# RAMP_V1-4.net
KiCad netlist of a schematic drawn in Altium Designer
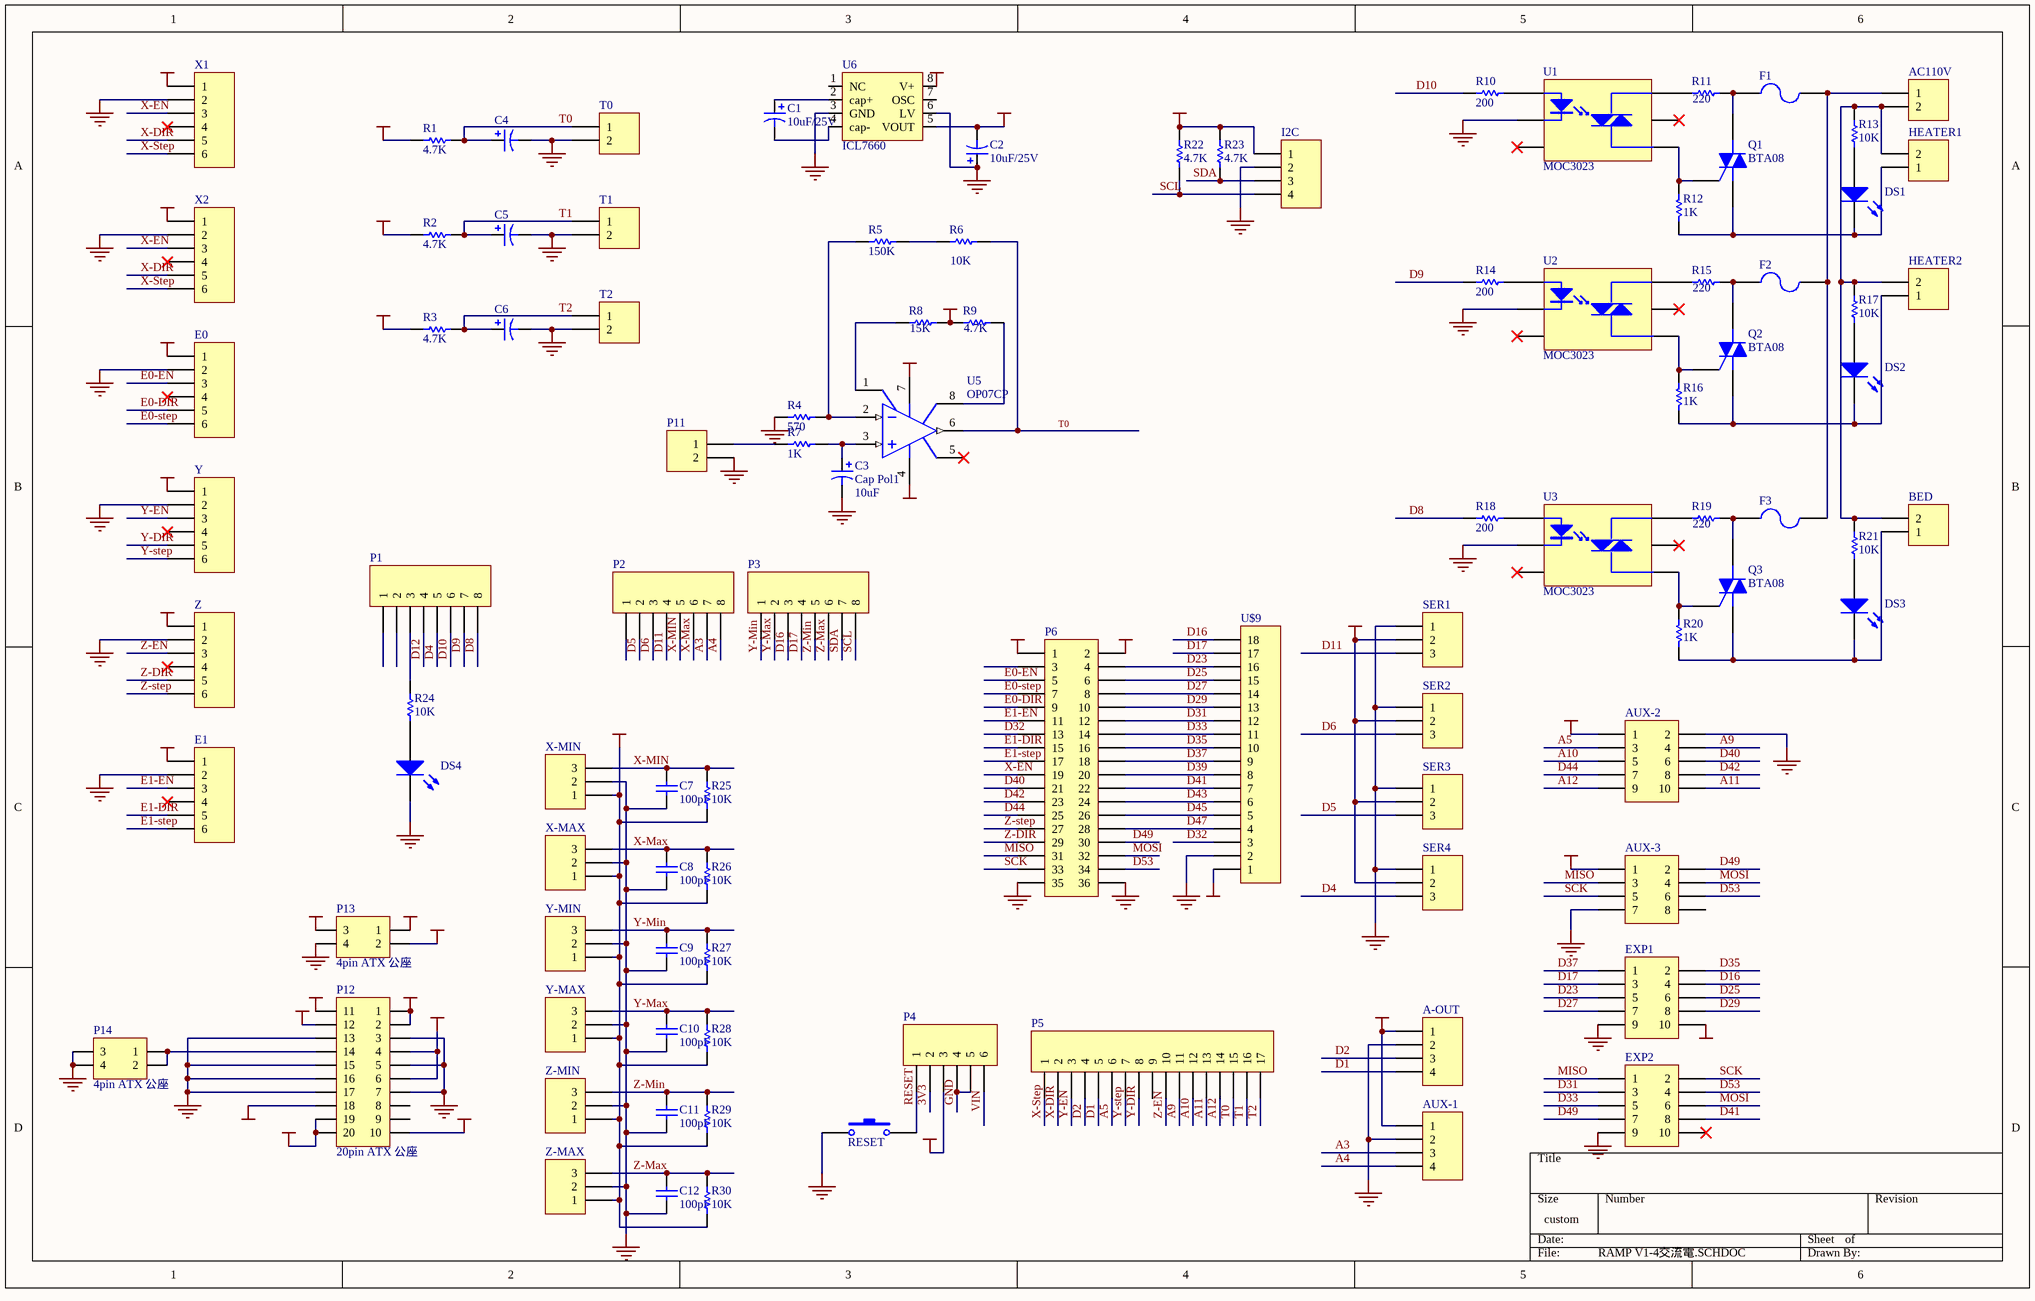
[diagram p0: RAMP V1-4交流電.SCHDOC]

(export (version "E")
  (design (tool "Eeschema 10.0.6"))
  (components
    (comp (ref "A-OUT")
      (value "Header 4")
      (footprint "HDR1X4")
      (description "Header, 4-Pin")
      (libsource (lib "Miscellaneous Connectors") (part "Header 4"))
    )
    (comp (ref "AC110V")
      (value "Header 2")
      (footprint "2PIN端子-1")
      (description "Header, 2-Pin")
      (libsource (lib "") (part "Header 2_2"))
    )
    (comp (ref "AUX-1")
      (value "Header 4")
      (footprint "HDR1X4")
      (description "Header, 4-Pin")
      (libsource (lib "Miscellaneous Connectors") (part "Header 4"))
    )
    (comp (ref "AUX-2")
      (value "Header 5X2")
      (footprint "HDR2X5")
      (description "Header, 5-Pin, Dual row")
      (libsource (lib "Miscellaneous Connectors") (part "Header 5X2"))
    )
    (comp (ref "AUX-3")
      (value "Header 4X2")
      (footprint "HDR2X4")
      (description "Header, 4-Pin, Dual row")
      (libsource (lib "Miscellaneous Connectors") (part "Header 4X2"))
    )
    (comp (ref "BED")
      (value "Header 2")
      (footprint "2PIN端子-1")
      (description "Header, 2-Pin")
      (libsource (lib "Miscellaneous Connectors") (part "Header 2"))
    )
    (comp (ref "C1")
      (value "10uF/25V")
      (footprint "CAPPR5-5x5")
      (description "Polarized Capacitor (Radial)")
      (fields (field (name "Comment") "Cap Pol1"))
      (libsource (lib "Miscellaneous Devices") (part "Cap Pol1"))
    )
    (comp (ref "C2")
      (value "10uF/25V")
      (footprint "CAPPR5-5x5")
      (description "Polarized Capacitor (Radial)")
      (fields (field (name "Comment") "Cap Pol1"))
      (libsource (lib "Miscellaneous Devices") (part "Cap Pol1"))
    )
    (comp (ref "C3")
      (value "Cap Pol1")
      (footprint "CAPPR5-5x5")
      (description "Polarized Capacitor (Radial)")
      (fields (field (name "ALTIUM_VALUE") "10uF"))
      (libsource (lib "Miscellaneous Devices") (part "Cap Pol1"))
    )
    (comp (ref "C4")
      (value "Cap Pol1")
      (footprint "CAPPR2-5x6.8")
      (description "Polarized Capacitor (Radial)")
      (libsource (lib "Miscellaneous Devices") (part "Cap Pol1"))
    )
    (comp (ref "C5")
      (value "Cap Pol1")
      (footprint "CAPPR2-5x6.8")
      (description "Polarized Capacitor (Radial)")
      (libsource (lib "Miscellaneous Devices") (part "Cap Pol1"))
    )
    (comp (ref "C6")
      (value "Cap Pol1")
      (footprint "CAPPR2-5x6.8")
      (description "Polarized Capacitor (Radial)")
      (libsource (lib "Miscellaneous Devices") (part "Cap Pol1"))
    )
    (comp (ref "C7")
      (value "100pF")
      (footprint "CAPR2.54-5.1x3.2")
      (description "Capacitor")
      (fields (field (name "Comment") "Cap"))
      (libsource (lib "Miscellaneous Devices") (part "Cap"))
    )
    (comp (ref "C8")
      (value "100pF")
      (footprint "CAPR2.54-5.1x3.2")
      (description "Capacitor")
      (fields (field (name "Comment") "Cap"))
      (libsource (lib "Miscellaneous Devices") (part "Cap"))
    )
    (comp (ref "C9")
      (value "100pF")
      (footprint "CAPR2.54-5.1x3.2")
      (description "Capacitor")
      (fields (field (name "Comment") "Cap"))
      (libsource (lib "Miscellaneous Devices") (part "Cap"))
    )
    (comp (ref "C10")
      (value "100pF")
      (footprint "CAPR2.54-5.1x3.2")
      (description "Capacitor")
      (fields (field (name "Comment") "Cap"))
      (libsource (lib "Miscellaneous Devices") (part "Cap"))
    )
    (comp (ref "C11")
      (value "100pF")
      (footprint "CAPR2.54-5.1x3.2")
      (description "Capacitor")
      (fields (field (name "Comment") "Cap"))
      (libsource (lib "Miscellaneous Devices") (part "Cap"))
    )
    (comp (ref "C12")
      (value "100pF")
      (footprint "CAPR2.54-5.1x3.2")
      (description "Capacitor")
      (fields (field (name "Comment") "Cap"))
      (libsource (lib "Miscellaneous Devices") (part "Cap"))
    )
    (comp (ref "DS1")
      (value "LED0")
      (footprint "LED-2")
      (description "Typical INFRARED GaAs LED")
      (libsource (lib "Miscellaneous Devices") (part "LED0"))
    )
    (comp (ref "DS2")
      (value "LED0")
      (footprint "LED-2")
      (description "Typical INFRARED GaAs LED")
      (libsource (lib "Miscellaneous Devices") (part "LED0"))
    )
    (comp (ref "DS3")
      (value "LED0")
      (footprint "LED-2")
      (description "Typical INFRARED GaAs LED")
      (libsource (lib "Miscellaneous Devices") (part "LED0"))
    )
    (comp (ref "DS4")
      (value "LED0")
      (footprint "LED-2")
      (description "Typical INFRARED GaAs LED")
      (libsource (lib "Miscellaneous Devices") (part "LED0"))
    )
    (comp (ref "E0")
      (value "Header 6")
      (footprint "2.54mm 6pin")
      (description "Header, 6-Pin")
      (libsource (lib "Miscellaneous Connectors") (part "Header 6"))
    )
    (comp (ref "E1")
      (value "Header 6")
      (footprint "2.54mm 6pin")
      (description "Header, 6-Pin")
      (libsource (lib "Miscellaneous Connectors") (part "Header 6"))
    )
    (comp (ref "EXP1")
      (value "Header 5X2")
      (footprint "10pin牛角公座")
      (description "Header, 5-Pin, Dual row")
      (libsource (lib "Miscellaneous Connectors") (part "Header 5X2"))
    )
    (comp (ref "EXP2")
      (value "Header 5X2")
      (footprint "10pin牛角公座")
      (description "Header, 5-Pin, Dual row")
      (libsource (lib "Miscellaneous Connectors") (part "Header 5X2"))
    )
    (comp (ref "F1")
      (value "Fuse 2")
      (footprint "保險絲座")
      (description "Fuse")
      (libsource (lib "Miscellaneous Devices") (part "Fuse 2"))
    )
    (comp (ref "F2")
      (value "Fuse 2")
      (footprint "保險絲座")
      (description "Fuse")
      (libsource (lib "Miscellaneous Devices") (part "Fuse 2"))
    )
    (comp (ref "F3")
      (value "Fuse 2")
      (footprint "保險絲座")
      (description "Fuse")
      (libsource (lib "Miscellaneous Devices") (part "Fuse 2"))
    )
    (comp (ref "HEATER1")
      (value "Header 2")
      (footprint "2PIN端子-1")
      (description "Header, 2-Pin")
      (libsource (lib "Miscellaneous Connectors") (part "Header 2"))
    )
    (comp (ref "HEATER2")
      (value "Header 2")
      (footprint "2PIN端子-1")
      (description "Header, 2-Pin")
      (libsource (lib "Miscellaneous Connectors") (part "Header 2"))
    )
    (comp (ref "I2C")
      (value "Header 4")
      (footprint "HDR1X4")
      (description "Header, 4-Pin")
      (libsource (lib "Miscellaneous Connectors") (part "Header 4"))
    )
    (comp (ref "P1")
      (value "Header 8")
      (footprint "HDR1X8")
      (description "Header, 8-Pin")
      (libsource (lib "") (part "Header 8_1"))
    )
    (comp (ref "P2")
      (value "Header 8")
      (footprint "HDR1X8")
      (description "Header, 8-Pin")
      (libsource (lib "Miscellaneous Connectors") (part "Header 8"))
    )
    (comp (ref "P3")
      (value "Header 8")
      (footprint "HDR1X8")
      (description "Header, 8-Pin")
      (libsource (lib "Miscellaneous Connectors") (part "Header 8"))
    )
    (comp (ref "P4")
      (value "Header 6")
      (footprint "HDR1X6")
      (description "Header, 6-Pin")
      (libsource (lib "") (part "Header 6_1"))
    )
    (comp (ref "P5")
      (value "Header 17")
      (footprint "HDR1X17")
      (description "Header, 17-Pin")
      (libsource (lib "Miscellaneous Connectors") (part "Header 17"))
    )
    (comp (ref "P6")
      (value "Header 18X2")
      (footprint "HDR2X18")
      (description "Header, 18-Pin, Dual row")
      (libsource (lib "Miscellaneous Connectors") (part "Header 18X2"))
    )
    (comp (ref "P11")
      (value "Header 2")
      (footprint "2PINºÝ¤l¥x¦³¦Õ")
      (description "Header, 2-Pin")
      (libsource (lib "") (part "Header 2_1"))
    )
    (comp (ref "P12")
      (value "20pin ATX 公座")
      (footprint "4.2mm 20pin")
      (libsource (lib "mydata") (part "20pin ATX 公座"))
    )
    (comp (ref "P13")
      (value "4pin ATX 公座")
      (footprint "4.2mm 4pin")
      (libsource (lib "mydata") (part "4pin ATX 公座"))
    )
    (comp (ref "P14")
      (value "4pin ATX 公座")
      (footprint "4.2mm 4pin")
      (libsource (lib "mydata") (part "4pin ATX 公座"))
    )
    (comp (ref "Q1")
      (value "BTA08")
      (footprint "SFM-T3/X1.6V")
      (description "Silicon Bidirectional Triode Thyristor")
      (libsource (lib "Miscellaneous Devices") (part "Triac"))
    )
    (comp (ref "Q2")
      (value "BTA08")
      (footprint "SFM-T3/X1.6V")
      (description "Silicon Bidirectional Triode Thyristor")
      (libsource (lib "Miscellaneous Devices") (part "Triac"))
    )
    (comp (ref "Q3")
      (value "BTA08")
      (footprint "SFM-T3/X1.6V")
      (description "Silicon Bidirectional Triode Thyristor")
      (libsource (lib "Miscellaneous Devices") (part "Triac"))
    )
    (comp (ref "R1")
      (value "4.7K")
      (footprint "AXIAL-0.3")
      (description "Resistor")
      (fields (field (name "Comment") "Res1"))
      (libsource (lib "Miscellaneous Devices") (part "Res1"))
    )
    (comp (ref "R2")
      (value "4.7K")
      (footprint "AXIAL-0.3")
      (description "Resistor")
      (fields (field (name "Comment") "Res1"))
      (libsource (lib "Miscellaneous Devices") (part "Res1"))
    )
    (comp (ref "R3")
      (value "4.7K")
      (footprint "AXIAL-0.3")
      (description "Resistor")
      (fields (field (name "Comment") "Res1"))
      (libsource (lib "Miscellaneous Devices") (part "Res1"))
    )
    (comp (ref "R4")
      (value "570")
      (footprint "AXIAL-0.3")
      (description "Resistor")
      (fields (field (name "Comment") "Res1"))
      (libsource (lib "Miscellaneous Devices") (part "Res1"))
    )
    (comp (ref "R5")
      (value "150K")
      (footprint "AXIAL-0.3")
      (description "Resistor")
      (fields (field (name "Comment") "Res1"))
      (libsource (lib "Miscellaneous Devices") (part "Res1"))
    )
    (comp (ref "R6")
      (value "10K")
      (footprint "AXIAL-0.3")
      (description "Resistor")
      (fields (field (name "Comment") "Res1"))
      (libsource (lib "Miscellaneous Devices") (part "Res1"))
    )
    (comp (ref "R7")
      (value "1K")
      (footprint "AXIAL-0.3")
      (description "Resistor")
      (fields (field (name "Comment") "Res1"))
      (libsource (lib "Miscellaneous Devices") (part "Res1"))
    )
    (comp (ref "R8")
      (value "15K")
      (footprint "AXIAL-0.3")
      (description "Resistor")
      (fields (field (name "Comment") "Res1"))
      (libsource (lib "Miscellaneous Devices") (part "Res1"))
    )
    (comp (ref "R9")
      (value "4.7K")
      (footprint "AXIAL-0.3")
      (description "Resistor")
      (fields (field (name "Comment") "Res1"))
      (libsource (lib "Miscellaneous Devices") (part "Res1"))
    )
    (comp (ref "R10")
      (value "200")
      (footprint "AXIAL-0.4")
      (description "Resistor")
      (fields (field (name "Comment") "Res1"))
      (libsource (lib "Miscellaneous Devices") (part "Res1"))
    )
    (comp (ref "R11")
      (value "220")
      (footprint "AXIAL-0.7")
      (description "Resistor")
      (fields (field (name "Comment") "Res1"))
      (libsource (lib "Miscellaneous Devices") (part "Res1"))
    )
    (comp (ref "R12")
      (value "1K")
      (footprint "AXIAL-0.6")
      (description "Resistor")
      (fields (field (name "Comment") "Res1"))
      (libsource (lib "") (part "Res1_1"))
    )
    (comp (ref "R13")
      (value "10K")
      (footprint "AXIAL-0.3")
      (description "Resistor")
      (fields (field (name "Comment") "Res1"))
      (libsource (lib "Miscellaneous Devices") (part "Res1"))
    )
    (comp (ref "R14")
      (value "200")
      (footprint "AXIAL-0.4")
      (description "Resistor")
      (fields (field (name "Comment") "Res1"))
      (libsource (lib "Miscellaneous Devices") (part "Res1"))
    )
    (comp (ref "R15")
      (value "220")
      (footprint "AXIAL-0.7")
      (description "Resistor")
      (fields (field (name "Comment") "Res1"))
      (libsource (lib "Miscellaneous Devices") (part "Res1"))
    )
    (comp (ref "R16")
      (value "1K")
      (footprint "AXIAL-0.6")
      (description "Resistor")
      (fields (field (name "Comment") "Res1"))
      (libsource (lib "") (part "Res1_1"))
    )
    (comp (ref "R17")
      (value "10K")
      (footprint "AXIAL-0.3")
      (description "Resistor")
      (fields (field (name "Comment") "Res1"))
      (libsource (lib "Miscellaneous Devices") (part "Res1"))
    )
    (comp (ref "R18")
      (value "200")
      (footprint "AXIAL-0.4")
      (description "Resistor")
      (fields (field (name "Comment") "Res1"))
      (libsource (lib "Miscellaneous Devices") (part "Res1"))
    )
    (comp (ref "R19")
      (value "220")
      (footprint "AXIAL-0.7")
      (description "Resistor")
      (fields (field (name "Comment") "Res1"))
      (libsource (lib "Miscellaneous Devices") (part "Res1"))
    )
    (comp (ref "R20")
      (value "1K")
      (footprint "AXIAL-0.6")
      (description "Resistor")
      (fields (field (name "Comment") "Res1"))
      (libsource (lib "") (part "Res1_1"))
    )
    (comp (ref "R21")
      (value "10K")
      (footprint "AXIAL-0.3")
      (description "Resistor")
      (fields (field (name "Comment") "Res1"))
      (libsource (lib "Miscellaneous Devices") (part "Res1"))
    )
    (comp (ref "R22")
      (value "4.7K")
      (footprint "AXIAL-0.3")
      (description "Resistor")
      (fields (field (name "Comment") "Res1"))
      (libsource (lib "Miscellaneous Devices") (part "Res1"))
    )
    (comp (ref "R23")
      (value "4.7K")
      (footprint "AXIAL-0.3")
      (description "Resistor")
      (fields (field (name "Comment") "Res1"))
      (libsource (lib "Miscellaneous Devices") (part "Res1"))
    )
    (comp (ref "R24")
      (value "10K")
      (footprint "AXIAL-0.3")
      (description "Resistor")
      (fields (field (name "Comment") "Res1"))
      (libsource (lib "Miscellaneous Devices") (part "Res1"))
    )
    (comp (ref "R25")
      (value "10K")
      (footprint "AXIAL-0.3")
      (description "Resistor")
      (fields (field (name "Comment") "Res1"))
      (libsource (lib "Miscellaneous Devices") (part "Res1"))
    )
    (comp (ref "R26")
      (value "10K")
      (footprint "AXIAL-0.3")
      (description "Resistor")
      (fields (field (name "Comment") "Res1"))
      (libsource (lib "Miscellaneous Devices") (part "Res1"))
    )
    (comp (ref "R27")
      (value "10K")
      (footprint "AXIAL-0.3")
      (description "Resistor")
      (fields (field (name "Comment") "Res1"))
      (libsource (lib "Miscellaneous Devices") (part "Res1"))
    )
    (comp (ref "R28")
      (value "10K")
      (footprint "AXIAL-0.3")
      (description "Resistor")
      (fields (field (name "Comment") "Res1"))
      (libsource (lib "Miscellaneous Devices") (part "Res1"))
    )
    (comp (ref "R29")
      (value "10K")
      (footprint "AXIAL-0.3")
      (description "Resistor")
      (fields (field (name "Comment") "Res1"))
      (libsource (lib "Miscellaneous Devices") (part "Res1"))
    )
    (comp (ref "R30")
      (value "10K")
      (footprint "AXIAL-0.3")
      (description "Resistor")
      (fields (field (name "Comment") "Res1"))
      (libsource (lib "Miscellaneous Devices") (part "Res1"))
    )
    (comp (ref "RESET")
      (value "SW-PB")
      (footprint "SW DIP4-2")
      (description "Switch")
      (libsource (lib "Miscellaneous Devices") (part "SW-PB"))
    )
    (comp (ref "SER1")
      (value "Header 3")
      (footprint "HDR1X3")
      (description "Header, 3-Pin")
      (libsource (lib "Miscellaneous Connectors") (part "Header 3"))
    )
    (comp (ref "SER2")
      (value "Header 3")
      (footprint "HDR1X3")
      (description "Header, 3-Pin")
      (libsource (lib "Miscellaneous Connectors") (part "Header 3"))
    )
    (comp (ref "SER3")
      (value "Header 3")
      (footprint "HDR1X3")
      (description "Header, 3-Pin")
      (libsource (lib "Miscellaneous Connectors") (part "Header 3"))
    )
    (comp (ref "SER4")
      (value "Header 3")
      (footprint "HDR1X3")
      (description "Header, 3-Pin")
      (libsource (lib "Miscellaneous Connectors") (part "Header 3"))
    )
    (comp (ref "T0")
      (value "Header 2")
      (footprint "HDR1X2")
      (description "Header, 2-Pin")
      (libsource (lib "") (part "Header 2_2"))
    )
    (comp (ref "T1")
      (value "Header 2")
      (footprint "HDR1X2")
      (description "Header, 2-Pin")
      (libsource (lib "") (part "Header 2_2"))
    )
    (comp (ref "T2")
      (value "Header 2")
      (footprint "HDR1X2")
      (description "Header, 2-Pin")
      (libsource (lib "") (part "Header 2_2"))
    )
    (comp (ref "U$9")
      (value "Header 18")
      (footprint "HDR1X18")
      (description "Header, 18-Pin")
      (libsource (lib "Miscellaneous Connectors") (part "Header 18"))
    )
    (comp (ref "U1")
      (value "MOC3023")
      (footprint "Dual-In-Line Package:DIP-6")
      (libsource (lib "mydata") (part "MOC3023"))
    )
    (comp (ref "U2")
      (value "MOC3023")
      (footprint "Dual-In-Line Package:DIP-6")
      (libsource (lib "mydata") (part "MOC3023"))
    )
    (comp (ref "U3")
      (value "MOC3023")
      (footprint "Dual-In-Line Package:DIP-6")
      (libsource (lib "mydata") (part "MOC3023"))
    )
    (comp (ref "U5")
      (value "OP07CP")
      (footprint "DIP-8")
      (description "Ultra-Low Offset Voltage Operational Amplifier")
      (libsource (lib "AD Operational Amplifier") (part "OP07CP"))
    )
    (comp (ref "U6")
      (value "ICL7660")
      (footprint "Dual-In-Line Package:DIP-8")
      (libsource (lib "mydata") (part "ICL7660"))
    )
    (comp (ref "X-MAX")
      (value "Header 3")
      (footprint "2.54mm 3pin")
      (description "Header, 3-Pin")
      (libsource (lib "") (part "Header 3_1"))
    )
    (comp (ref "X-MIN")
      (value "Header 3")
      (footprint "2.54mm 3pin")
      (description "Header, 3-Pin")
      (libsource (lib "") (part "Header 3_2"))
    )
    (comp (ref "X1")
      (value "Header 6")
      (footprint "2.54mm 6pin")
      (description "Header, 6-Pin")
      (libsource (lib "Miscellaneous Connectors") (part "Header 6"))
    )
    (comp (ref "X2")
      (value "Header 6")
      (footprint "2.54mm 6pin")
      (description "Header, 6-Pin")
      (libsource (lib "Miscellaneous Connectors") (part "Header 6"))
    )
    (comp (ref "Y")
      (value "Header 6")
      (footprint "2.54mm 6pin")
      (description "Header, 6-Pin")
      (libsource (lib "Miscellaneous Connectors") (part "Header 6"))
    )
    (comp (ref "Y-MAX")
      (value "Header 3")
      (footprint "2.54mm 3pin")
      (description "Header, 3-Pin")
      (libsource (lib "") (part "Header 3_1"))
    )
    (comp (ref "Y-MIN")
      (value "Header 3")
      (footprint "2.54mm 3pin")
      (description "Header, 3-Pin")
      (libsource (lib "") (part "Header 3_1"))
    )
    (comp (ref "Z")
      (value "Header 6")
      (footprint "2.54mm 6pin")
      (description "Header, 6-Pin")
      (libsource (lib "Miscellaneous Connectors") (part "Header 6"))
    )
    (comp (ref "Z-MAX")
      (value "Header 3")
      (footprint "2.54mm 3pin")
      (description "Header, 3-Pin")
      (libsource (lib "") (part "Header 3_1"))
    )
    (comp (ref "Z-MIN")
      (value "Header 3")
      (footprint "2.54mm 3pin")
      (description "Header, 3-Pin")
      (libsource (lib "") (part "Header 3_1"))
    )
  )
  (nets
    (net (code "1") (name "+3-3") (class "Default")
      (node (ref "P12") (pin "1") (pinfunction "1_1") (pintype "passive"))
      (node (ref "P12") (pin "11") (pinfunction "11_11") (pintype "passive"))
      (node (ref "P12") (pin "2") (pinfunction "2_2") (pintype "passive"))
      (node (ref "P13") (pin "2") (pinfunction "2_2") (pintype "passive"))
    )
    (net (code "2") (name "+5") (class "Default")
      (node (ref "A-OUT") (pin "1") (pinfunction "1_1") (pintype "passive"))
      (node (ref "AUX-1") (pin "1") (pinfunction "1_1") (pintype "passive"))
      (node (ref "AUX-2") (pin "1") (pinfunction "1_1") (pintype "passive"))
      (node (ref "AUX-3") (pin "1") (pinfunction "1_1") (pintype "passive"))
      (node (ref "E0") (pin "1") (pinfunction "1_1") (pintype "passive"))
      (node (ref "E1") (pin "1") (pinfunction "1_1") (pintype "passive"))
      (node (ref "EXP1") (pin "10") (pinfunction "10_10") (pintype "passive"))
      (node (ref "I2C") (pin "1") (pinfunction "1_1") (pintype "passive"))
      (node (ref "P12") (pin "19") (pinfunction "19_19") (pintype "passive"))
      (node (ref "P12") (pin "20") (pinfunction "20_20") (pintype "passive"))
      (node (ref "P12") (pin "4") (pinfunction "4_4") (pintype "passive"))
      (node (ref "P12") (pin "6") (pinfunction "6_6") (pintype "passive"))
      (node (ref "P4") (pin "3") (pinfunction "3_3") (pintype "passive"))
      (node (ref "P6") (pin "1") (pinfunction "1_1") (pintype "passive"))
      (node (ref "P6") (pin "2") (pinfunction "2_2") (pintype "passive"))
      (node (ref "R1") (pin "1") (pinfunction "1_1") (pintype "passive"))
      (node (ref "R2") (pin "1") (pinfunction "1_1") (pintype "passive"))
      (node (ref "R22") (pin "2") (pinfunction "2_2") (pintype "passive"))
      (node (ref "R23") (pin "2") (pinfunction "2_2") (pintype "passive"))
      (node (ref "R25") (pin "1") (pinfunction "1_1") (pintype "passive"))
      (node (ref "R26") (pin "1") (pinfunction "1_1") (pintype "passive"))
      (node (ref "R27") (pin "1") (pinfunction "1_1") (pintype "passive"))
      (node (ref "R28") (pin "1") (pinfunction "1_1") (pintype "passive"))
      (node (ref "R29") (pin "1") (pinfunction "1_1") (pintype "passive"))
      (node (ref "R3") (pin "1") (pinfunction "1_1") (pintype "passive"))
      (node (ref "R30") (pin "1") (pinfunction "1_1") (pintype "passive"))
      (node (ref "R8") (pin "2") (pinfunction "2_2") (pintype "passive"))
      (node (ref "R9") (pin "1") (pinfunction "1_1") (pintype "passive"))
      (node (ref "SER1") (pin "2") (pinfunction "2_2") (pintype "passive"))
      (node (ref "SER2") (pin "2") (pinfunction "2_2") (pintype "passive"))
      (node (ref "SER3") (pin "2") (pinfunction "2_2") (pintype "passive"))
      (node (ref "SER4") (pin "2") (pinfunction "2_2") (pintype "passive"))
      (node (ref "U$9") (pin "1") (pinfunction "1_1") (pintype "passive"))
      (node (ref "U5") (pin "7") (pinfunction "V+_7") (pintype "power_in"))
      (node (ref "U6") (pin "8") (pinfunction "V+_8") (pintype "passive"))
      (node (ref "X-MAX") (pin "1") (pinfunction "1_1") (pintype "passive"))
      (node (ref "X-MIN") (pin "1") (pinfunction "1_1") (pintype "passive"))
      (node (ref "X1") (pin "1") (pinfunction "1_1") (pintype "passive"))
      (node (ref "X2") (pin "1") (pinfunction "1_1") (pintype "passive"))
      (node (ref "Y") (pin "1") (pinfunction "1_1") (pintype "passive"))
      (node (ref "Y-MAX") (pin "1") (pinfunction "1_1") (pintype "passive"))
      (node (ref "Y-MIN") (pin "1") (pinfunction "1_1") (pintype "passive"))
      (node (ref "Z") (pin "1") (pinfunction "1_1") (pintype "passive"))
      (node (ref "Z-MAX") (pin "1") (pinfunction "1_1") (pintype "passive"))
      (node (ref "Z-MIN") (pin "1") (pinfunction "1_1") (pintype "passive"))
    )
    (net (code "3") (name "+12") (class "Default")
      (node (ref "P12") (pin "10") (pinfunction "10_10") (pintype "passive"))
      (node (ref "P13") (pin "1") (pinfunction "1_1") (pintype "passive"))
    )
    (net (code "4") (name "-5") (class "Default")
      (node (ref "C2") (pin "2") (pinfunction "2_2") (pintype "passive"))
      (node (ref "P12") (pin "18") (pinfunction "18_18") (pintype "passive"))
      (node (ref "U5") (pin "4") (pinfunction "V-_4") (pintype "power_in"))
      (node (ref "U6") (pin "5") (pinfunction "VOUT_5") (pintype "passive"))
    )
    (net (code "5") (name "-12") (class "Default")
      (node (ref "P12") (pin "12") (pinfunction "12_12") (pintype "passive"))
    )
    (net (code "6") (name "/3V3") (class "Default")
      (node (ref "P4") (pin "2") (pinfunction "2_2") (pintype "passive"))
    )
    (net (code "7") (name "/A3") (class "Default")
      (node (ref "AUX-1") (pin "3") (pinfunction "3_3") (pintype "passive"))
      (node (ref "P2") (pin "7") (pinfunction "7_7") (pintype "passive"))
    )
    (net (code "8") (name "/A4") (class "Default")
      (node (ref "AUX-1") (pin "4") (pinfunction "4_4") (pintype "passive"))
      (node (ref "P2") (pin "8") (pinfunction "8_8") (pintype "passive"))
    )
    (net (code "9") (name "/A5") (class "Default")
      (node (ref "AUX-2") (pin "3") (pinfunction "3_3") (pintype "passive"))
      (node (ref "P5") (pin "6") (pinfunction "6_6") (pintype "passive"))
    )
    (net (code "10") (name "/A9") (class "Default")
      (node (ref "AUX-2") (pin "4") (pinfunction "4_4") (pintype "passive"))
      (node (ref "P5") (pin "11") (pinfunction "11_11") (pintype "passive"))
    )
    (net (code "11") (name "/A10") (class "Default")
      (node (ref "AUX-2") (pin "5") (pinfunction "5_5") (pintype "passive"))
      (node (ref "P5") (pin "12") (pinfunction "12_12") (pintype "passive"))
    )
    (net (code "12") (name "/A11") (class "Default")
      (node (ref "AUX-2") (pin "10") (pinfunction "10_10") (pintype "passive"))
      (node (ref "P5") (pin "13") (pinfunction "13_13") (pintype "passive"))
    )
    (net (code "13") (name "/A12") (class "Default")
      (node (ref "AUX-2") (pin "9") (pinfunction "9_9") (pintype "passive"))
      (node (ref "P5") (pin "14") (pinfunction "14_14") (pintype "passive"))
    )
    (net (code "14") (name "/D1") (class "Default")
      (node (ref "A-OUT") (pin "4") (pinfunction "4_4") (pintype "passive"))
      (node (ref "P5") (pin "5") (pinfunction "5_5") (pintype "passive"))
    )
    (net (code "15") (name "/D2") (class "Default")
      (node (ref "A-OUT") (pin "3") (pinfunction "3_3") (pintype "passive"))
      (node (ref "P5") (pin "4") (pinfunction "4_4") (pintype "passive"))
    )
    (net (code "16") (name "/D4") (class "Default")
      (node (ref "P1") (pin "5") (pinfunction "5_5") (pintype "passive"))
      (node (ref "SER4") (pin "3") (pinfunction "3_3") (pintype "passive"))
    )
    (net (code "17") (name "/D5") (class "Default")
      (node (ref "P2") (pin "2") (pinfunction "2_2") (pintype "passive"))
      (node (ref "SER3") (pin "3") (pinfunction "3_3") (pintype "passive"))
    )
    (net (code "18") (name "/D6") (class "Default")
      (node (ref "P2") (pin "3") (pinfunction "3_3") (pintype "passive"))
      (node (ref "SER2") (pin "3") (pinfunction "3_3") (pintype "passive"))
    )
    (net (code "19") (name "/D8") (class "Default")
      (node (ref "P1") (pin "8") (pinfunction "8_8") (pintype "passive"))
      (node (ref "R18") (pin "1") (pinfunction "1_1") (pintype "passive"))
    )
    (net (code "20") (name "/D9") (class "Default")
      (node (ref "P1") (pin "7") (pinfunction "7_7") (pintype "passive"))
      (node (ref "R14") (pin "1") (pinfunction "1_1") (pintype "passive"))
    )
    (net (code "21") (name "/D10") (class "Default")
      (node (ref "P1") (pin "6") (pinfunction "6_6") (pintype "passive"))
      (node (ref "R10") (pin "1") (pinfunction "1_1") (pintype "passive"))
    )
    (net (code "22") (name "/D11") (class "Default")
      (node (ref "P2") (pin "4") (pinfunction "4_4") (pintype "passive"))
      (node (ref "SER1") (pin "3") (pinfunction "3_3") (pintype "passive"))
    )
    (net (code "23") (name "/D12") (class "Default")
      (node (ref "P1") (pin "4") (pinfunction "4_4") (pintype "passive"))
    )
    (net (code "24") (name "/D16") (class "Default")
      (node (ref "EXP1") (pin "4") (pinfunction "4_4") (pintype "passive"))
      (node (ref "P3") (pin "3") (pinfunction "3_3") (pintype "passive"))
      (node (ref "U$9") (pin "18") (pinfunction "18_18") (pintype "passive"))
    )
    (net (code "25") (name "/D17") (class "Default")
      (node (ref "EXP1") (pin "3") (pinfunction "3_3") (pintype "passive"))
      (node (ref "P3") (pin "4") (pinfunction "4_4") (pintype "passive"))
      (node (ref "U$9") (pin "17") (pinfunction "17_17") (pintype "passive"))
    )
    (net (code "26") (name "/D23") (class "Default")
      (node (ref "EXP1") (pin "5") (pinfunction "5_5") (pintype "passive"))
      (node (ref "P6") (pin "4") (pinfunction "4_4") (pintype "passive"))
      (node (ref "U$9") (pin "16") (pinfunction "16_16") (pintype "passive"))
    )
    (net (code "27") (name "/D25") (class "Default")
      (node (ref "EXP1") (pin "6") (pinfunction "6_6") (pintype "passive"))
      (node (ref "P6") (pin "6") (pinfunction "6_6") (pintype "passive"))
      (node (ref "U$9") (pin "15") (pinfunction "15_15") (pintype "passive"))
    )
    (net (code "28") (name "/D27") (class "Default")
      (node (ref "EXP1") (pin "7") (pinfunction "7_7") (pintype "passive"))
      (node (ref "P6") (pin "8") (pinfunction "8_8") (pintype "passive"))
      (node (ref "U$9") (pin "14") (pinfunction "14_14") (pintype "passive"))
    )
    (net (code "29") (name "/D29") (class "Default")
      (node (ref "EXP1") (pin "8") (pinfunction "8_8") (pintype "passive"))
      (node (ref "P6") (pin "10") (pinfunction "10_10") (pintype "passive"))
      (node (ref "U$9") (pin "13") (pinfunction "13_13") (pintype "passive"))
    )
    (net (code "30") (name "/D31") (class "Default")
      (node (ref "EXP2") (pin "3") (pinfunction "3_3") (pintype "passive"))
      (node (ref "P6") (pin "12") (pinfunction "12_12") (pintype "passive"))
      (node (ref "U$9") (pin "12") (pinfunction "12_12") (pintype "passive"))
    )
    (net (code "31") (name "/D32") (class "Default")
      (node (ref "P6") (pin "13") (pinfunction "13_13") (pintype "passive"))
      (node (ref "U$9") (pin "3") (pinfunction "3_3") (pintype "passive"))
    )
    (net (code "32") (name "/D33") (class "Default")
      (node (ref "EXP2") (pin "5") (pinfunction "5_5") (pintype "passive"))
      (node (ref "P6") (pin "14") (pinfunction "14_14") (pintype "passive"))
      (node (ref "U$9") (pin "11") (pinfunction "11_11") (pintype "passive"))
    )
    (net (code "33") (name "/D35") (class "Default")
      (node (ref "EXP1") (pin "2") (pinfunction "2_2") (pintype "passive"))
      (node (ref "P6") (pin "16") (pinfunction "16_16") (pintype "passive"))
      (node (ref "U$9") (pin "10") (pinfunction "10_10") (pintype "passive"))
    )
    (net (code "34") (name "/D37") (class "Default")
      (node (ref "EXP1") (pin "1") (pinfunction "1_1") (pintype "passive"))
      (node (ref "P6") (pin "18") (pinfunction "18_18") (pintype "passive"))
      (node (ref "U$9") (pin "9") (pinfunction "9_9") (pintype "passive"))
    )
    (net (code "35") (name "/D39") (class "Default")
      (node (ref "P6") (pin "20") (pinfunction "20_20") (pintype "passive"))
      (node (ref "U$9") (pin "8") (pinfunction "8_8") (pintype "passive"))
    )
    (net (code "36") (name "/D40") (class "Default")
      (node (ref "AUX-2") (pin "6") (pinfunction "6_6") (pintype "passive"))
      (node (ref "P6") (pin "21") (pinfunction "21_21") (pintype "passive"))
    )
    (net (code "37") (name "/D41") (class "Default")
      (node (ref "EXP2") (pin "8") (pinfunction "8_8") (pintype "passive"))
      (node (ref "P6") (pin "22") (pinfunction "22_22") (pintype "passive"))
      (node (ref "U$9") (pin "7") (pinfunction "7_7") (pintype "passive"))
    )
    (net (code "38") (name "/D42") (class "Default")
      (node (ref "AUX-2") (pin "8") (pinfunction "8_8") (pintype "passive"))
      (node (ref "P6") (pin "23") (pinfunction "23_23") (pintype "passive"))
    )
    (net (code "39") (name "/D43") (class "Default")
      (node (ref "P6") (pin "24") (pinfunction "24_24") (pintype "passive"))
      (node (ref "U$9") (pin "6") (pinfunction "6_6") (pintype "passive"))
    )
    (net (code "40") (name "/D44") (class "Default")
      (node (ref "AUX-2") (pin "7") (pinfunction "7_7") (pintype "passive"))
      (node (ref "P6") (pin "25") (pinfunction "25_25") (pintype "passive"))
    )
    (net (code "41") (name "/D45") (class "Default")
      (node (ref "P6") (pin "26") (pinfunction "26_26") (pintype "passive"))
      (node (ref "U$9") (pin "5") (pinfunction "5_5") (pintype "passive"))
    )
    (net (code "42") (name "/D47") (class "Default")
      (node (ref "P6") (pin "28") (pinfunction "28_28") (pintype "passive"))
      (node (ref "U$9") (pin "4") (pinfunction "4_4") (pintype "passive"))
    )
    (net (code "43") (name "/D49") (class "Default")
      (node (ref "AUX-3") (pin "2") (pinfunction "2_2") (pintype "passive"))
      (node (ref "EXP2") (pin "7") (pinfunction "7_7") (pintype "passive"))
      (node (ref "P6") (pin "30") (pinfunction "30_30") (pintype "passive"))
    )
    (net (code "44") (name "/D53") (class "Default")
      (node (ref "AUX-3") (pin "6") (pinfunction "6_6") (pintype "passive"))
      (node (ref "EXP2") (pin "4") (pinfunction "4_4") (pintype "passive"))
      (node (ref "P6") (pin "34") (pinfunction "34_34") (pintype "passive"))
    )
    (net (code "45") (name "/E0-DIR") (class "Default")
      (node (ref "E0") (pin "5") (pinfunction "5_5") (pintype "passive"))
      (node (ref "P6") (pin "9") (pinfunction "9_9") (pintype "passive"))
    )
    (net (code "46") (name "/E0-EN") (class "Default")
      (node (ref "E0") (pin "3") (pinfunction "3_3") (pintype "passive"))
      (node (ref "P6") (pin "5") (pinfunction "5_5") (pintype "passive"))
    )
    (net (code "47") (name "/E0-step") (class "Default")
      (node (ref "E0") (pin "6") (pinfunction "6_6") (pintype "passive"))
      (node (ref "P6") (pin "7") (pinfunction "7_7") (pintype "passive"))
    )
    (net (code "48") (name "/E1-DIR") (class "Default")
      (node (ref "E1") (pin "5") (pinfunction "5_5") (pintype "passive"))
      (node (ref "P6") (pin "15") (pinfunction "15_15") (pintype "passive"))
    )
    (net (code "49") (name "/E1-EN") (class "Default")
      (node (ref "E1") (pin "3") (pinfunction "3_3") (pintype "passive"))
      (node (ref "P6") (pin "11") (pinfunction "11_11") (pintype "passive"))
    )
    (net (code "50") (name "/E1-step") (class "Default")
      (node (ref "E1") (pin "6") (pinfunction "6_6") (pintype "passive"))
      (node (ref "P6") (pin "17") (pinfunction "17_17") (pintype "passive"))
    )
    (net (code "51") (name "/MISO") (class "Default")
      (node (ref "AUX-3") (pin "3") (pinfunction "3_3") (pintype "passive"))
      (node (ref "EXP2") (pin "1") (pinfunction "1_1") (pintype "passive"))
      (node (ref "P6") (pin "31") (pinfunction "31_31") (pintype "passive"))
    )
    (net (code "52") (name "/MOSI") (class "Default")
      (node (ref "AUX-3") (pin "4") (pinfunction "4_4") (pintype "passive"))
      (node (ref "EXP2") (pin "6") (pinfunction "6_6") (pintype "passive"))
      (node (ref "P6") (pin "32") (pinfunction "32_32") (pintype "passive"))
    )
    (net (code "53") (name "/RESET") (class "Default")
      (node (ref "P4") (pin "1") (pinfunction "1_1") (pintype "passive"))
      (node (ref "RESET") (pin "1") (pinfunction "1_1") (pintype "passive"))
    )
    (net (code "54") (name "/SCK") (class "Default")
      (node (ref "AUX-3") (pin "5") (pinfunction "5_5") (pintype "passive"))
      (node (ref "EXP2") (pin "2") (pinfunction "2_2") (pintype "passive"))
      (node (ref "P6") (pin "33") (pinfunction "33_33") (pintype "passive"))
    )
    (net (code "55") (name "/SCL") (class "Default")
      (node (ref "I2C") (pin "4") (pinfunction "4_4") (pintype "passive"))
      (node (ref "P3") (pin "8") (pinfunction "8_8") (pintype "passive"))
      (node (ref "R22") (pin "1") (pinfunction "1_1") (pintype "passive"))
    )
    (net (code "56") (name "/SDA") (class "Default")
      (node (ref "I2C") (pin "3") (pinfunction "3_3") (pintype "passive"))
      (node (ref "P3") (pin "7") (pinfunction "7_7") (pintype "passive"))
      (node (ref "R23") (pin "1") (pinfunction "1_1") (pintype "passive"))
    )
    (net (code "57") (name "/T0") (class "Default")
      (node (ref "C4") (pin "1") (pinfunction "1_1") (pintype "passive"))
      (node (ref "P5") (pin "15") (pinfunction "15_15") (pintype "passive"))
      (node (ref "R1") (pin "2") (pinfunction "2_2") (pintype "passive"))
      (node (ref "R6") (pin "2") (pinfunction "2_2") (pintype "passive"))
      (node (ref "T0") (pin "1") (pinfunction "1_1") (pintype "passive"))
      (node (ref "U5") (pin "6") (pinfunction "OUT_6") (pintype "output"))
    )
    (net (code "58") (name "/T1") (class "Default")
      (node (ref "C5") (pin "1") (pinfunction "1_1") (pintype "passive"))
      (node (ref "P5") (pin "16") (pinfunction "16_16") (pintype "passive"))
      (node (ref "R2") (pin "2") (pinfunction "2_2") (pintype "passive"))
      (node (ref "T1") (pin "1") (pinfunction "1_1") (pintype "passive"))
    )
    (net (code "59") (name "/T2") (class "Default")
      (node (ref "C6") (pin "1") (pinfunction "1_1") (pintype "passive"))
      (node (ref "P5") (pin "17") (pinfunction "17_17") (pintype "passive"))
      (node (ref "R3") (pin "2") (pinfunction "2_2") (pintype "passive"))
      (node (ref "T2") (pin "1") (pinfunction "1_1") (pintype "passive"))
    )
    (net (code "60") (name "/VIN") (class "Default")
      (node (ref "P4") (pin "6") (pinfunction "6_6") (pintype "passive"))
    )
    (net (code "61") (name "/X-DIR") (class "Default")
      (node (ref "P5") (pin "2") (pinfunction "2_2") (pintype "passive"))
      (node (ref "X1") (pin "5") (pinfunction "5_5") (pintype "passive"))
      (node (ref "X2") (pin "5") (pinfunction "5_5") (pintype "passive"))
    )
    (net (code "62") (name "/X-EN") (class "Default")
      (node (ref "P6") (pin "19") (pinfunction "19_19") (pintype "passive"))
      (node (ref "X1") (pin "3") (pinfunction "3_3") (pintype "passive"))
      (node (ref "X2") (pin "3") (pinfunction "3_3") (pintype "passive"))
    )
    (net (code "63") (name "/X-MIN") (class "Default")
      (node (ref "C7") (pin "2") (pinfunction "2_2") (pintype "passive"))
      (node (ref "P2") (pin "5") (pinfunction "5_5") (pintype "passive"))
      (node (ref "R25") (pin "2") (pinfunction "2_2") (pintype "passive"))
      (node (ref "X-MIN") (pin "3") (pinfunction "3_3") (pintype "passive"))
    )
    (net (code "64") (name "/X-Max") (class "Default")
      (node (ref "C8") (pin "2") (pinfunction "2_2") (pintype "passive"))
      (node (ref "P2") (pin "6") (pinfunction "6_6") (pintype "passive"))
      (node (ref "R26") (pin "2") (pinfunction "2_2") (pintype "passive"))
      (node (ref "X-MAX") (pin "3") (pinfunction "3_3") (pintype "passive"))
    )
    (net (code "65") (name "/X-Step") (class "Default")
      (node (ref "P5") (pin "1") (pinfunction "1_1") (pintype "passive"))
      (node (ref "X1") (pin "6") (pinfunction "6_6") (pintype "passive"))
      (node (ref "X2") (pin "6") (pinfunction "6_6") (pintype "passive"))
    )
    (net (code "66") (name "/Y-DIR") (class "Default")
      (node (ref "P5") (pin "8") (pinfunction "8_8") (pintype "passive"))
      (node (ref "Y") (pin "5") (pinfunction "5_5") (pintype "passive"))
    )
    (net (code "67") (name "/Y-EN") (class "Default")
      (node (ref "P5") (pin "3") (pinfunction "3_3") (pintype "passive"))
      (node (ref "Y") (pin "3") (pinfunction "3_3") (pintype "passive"))
    )
    (net (code "68") (name "/Y-Max") (class "Default")
      (node (ref "C10") (pin "2") (pinfunction "2_2") (pintype "passive"))
      (node (ref "P3") (pin "2") (pinfunction "2_2") (pintype "passive"))
      (node (ref "R28") (pin "2") (pinfunction "2_2") (pintype "passive"))
      (node (ref "Y-MAX") (pin "3") (pinfunction "3_3") (pintype "passive"))
    )
    (net (code "69") (name "/Y-Min") (class "Default")
      (node (ref "C9") (pin "2") (pinfunction "2_2") (pintype "passive"))
      (node (ref "P3") (pin "1") (pinfunction "1_1") (pintype "passive"))
      (node (ref "R27") (pin "2") (pinfunction "2_2") (pintype "passive"))
      (node (ref "Y-MIN") (pin "3") (pinfunction "3_3") (pintype "passive"))
    )
    (net (code "70") (name "/Y-step") (class "Default")
      (node (ref "P5") (pin "7") (pinfunction "7_7") (pintype "passive"))
      (node (ref "Y") (pin "6") (pinfunction "6_6") (pintype "passive"))
    )
    (net (code "71") (name "/Z-DIR") (class "Default")
      (node (ref "P6") (pin "29") (pinfunction "29_29") (pintype "passive"))
      (node (ref "Z") (pin "5") (pinfunction "5_5") (pintype "passive"))
    )
    (net (code "72") (name "/Z-EN") (class "Default")
      (node (ref "P5") (pin "10") (pinfunction "10_10") (pintype "passive"))
      (node (ref "Z") (pin "3") (pinfunction "3_3") (pintype "passive"))
    )
    (net (code "73") (name "/Z-Max") (class "Default")
      (node (ref "C12") (pin "2") (pinfunction "2_2") (pintype "passive"))
      (node (ref "P3") (pin "6") (pinfunction "6_6") (pintype "passive"))
      (node (ref "R30") (pin "2") (pinfunction "2_2") (pintype "passive"))
      (node (ref "Z-MAX") (pin "3") (pinfunction "3_3") (pintype "passive"))
    )
    (net (code "74") (name "/Z-Min") (class "Default")
      (node (ref "C11") (pin "2") (pinfunction "2_2") (pintype "passive"))
      (node (ref "P3") (pin "5") (pinfunction "5_5") (pintype "passive"))
      (node (ref "R29") (pin "2") (pinfunction "2_2") (pintype "passive"))
      (node (ref "Z-MIN") (pin "3") (pinfunction "3_3") (pintype "passive"))
    )
    (net (code "75") (name "/Z-step") (class "Default")
      (node (ref "P6") (pin "27") (pinfunction "27_27") (pintype "passive"))
      (node (ref "Z") (pin "6") (pinfunction "6_6") (pintype "passive"))
    )
    (net (code "76") (name "GND") (class "Default")
      (node (ref "A-OUT") (pin "2") (pinfunction "2_2") (pintype "passive"))
      (node (ref "AUX-1") (pin "2") (pinfunction "2_2") (pintype "passive"))
      (node (ref "AUX-2") (pin "2") (pinfunction "2_2") (pintype "passive"))
      (node (ref "AUX-3") (pin "7") (pinfunction "7_7") (pintype "passive"))
      (node (ref "C10") (pin "1") (pinfunction "1_1") (pintype "passive"))
      (node (ref "C11") (pin "1") (pinfunction "1_1") (pintype "passive"))
      (node (ref "C12") (pin "1") (pinfunction "1_1") (pintype "passive"))
      (node (ref "C2") (pin "1") (pinfunction "1_1") (pintype "passive"))
      (node (ref "C3") (pin "2") (pinfunction "2_2") (pintype "passive"))
      (node (ref "C4") (pin "2") (pinfunction "2_2") (pintype "passive"))
      (node (ref "C5") (pin "2") (pinfunction "2_2") (pintype "passive"))
      (node (ref "C6") (pin "2") (pinfunction "2_2") (pintype "passive"))
      (node (ref "C7") (pin "1") (pinfunction "1_1") (pintype "passive"))
      (node (ref "C8") (pin "1") (pinfunction "1_1") (pintype "passive"))
      (node (ref "C9") (pin "1") (pinfunction "1_1") (pintype "passive"))
      (node (ref "DS4") (pin "2") (pinfunction "K_2") (pintype "passive"))
      (node (ref "E0") (pin "2") (pinfunction "2_2") (pintype "passive"))
      (node (ref "E1") (pin "2") (pinfunction "2_2") (pintype "passive"))
      (node (ref "EXP1") (pin "9") (pinfunction "9_9") (pintype "passive"))
      (node (ref "EXP2") (pin "9") (pinfunction "9_9") (pintype "passive"))
      (node (ref "I2C") (pin "2") (pinfunction "2_2") (pintype "passive"))
      (node (ref "P11") (pin "2") (pinfunction "2_2") (pintype "passive"))
      (node (ref "P12") (pin "13") (pinfunction "13_13") (pintype "passive"))
      (node (ref "P12") (pin "15") (pinfunction "15_15") (pintype "passive"))
      (node (ref "P12") (pin "16") (pinfunction "16_16") (pintype "passive"))
      (node (ref "P12") (pin "17") (pinfunction "17_17") (pintype "passive"))
      (node (ref "P12") (pin "3") (pinfunction "3_3") (pintype "passive"))
      (node (ref "P12") (pin "5") (pinfunction "5_5") (pintype "passive"))
      (node (ref "P12") (pin "7") (pinfunction "7_7") (pintype "passive"))
      (node (ref "P13") (pin "4") (pinfunction "4_4") (pintype "passive"))
      (node (ref "P14") (pin "3") (pinfunction "3_3") (pintype "passive"))
      (node (ref "P14") (pin "4") (pinfunction "4_4") (pintype "passive"))
      (node (ref "P4") (pin "4") (pinfunction "4_4") (pintype "passive"))
      (node (ref "P4") (pin "5") (pinfunction "5_5") (pintype "passive"))
      (node (ref "P6") (pin "35") (pinfunction "35_35") (pintype "passive"))
      (node (ref "P6") (pin "36") (pinfunction "36_36") (pintype "passive"))
      (node (ref "R4") (pin "1") (pinfunction "1_1") (pintype "passive"))
      (node (ref "RESET") (pin "2") (pinfunction "2_2") (pintype "passive"))
      (node (ref "SER1") (pin "1") (pinfunction "1_1") (pintype "passive"))
      (node (ref "SER2") (pin "1") (pinfunction "1_1") (pintype "passive"))
      (node (ref "SER3") (pin "1") (pinfunction "1_1") (pintype "passive"))
      (node (ref "SER4") (pin "1") (pinfunction "1_1") (pintype "passive"))
      (node (ref "T0") (pin "2") (pinfunction "2_2") (pintype "passive"))
      (node (ref "T1") (pin "2") (pinfunction "2_2") (pintype "passive"))
      (node (ref "T2") (pin "2") (pinfunction "2_2") (pintype "passive"))
      (node (ref "U$9") (pin "2") (pinfunction "2_2") (pintype "passive"))
      (node (ref "U1") (pin "2") (pinfunction "C_2") (pintype "passive"))
      (node (ref "U2") (pin "2") (pinfunction "C_2") (pintype "passive"))
      (node (ref "U3") (pin "2") (pinfunction "C_2") (pintype "passive"))
      (node (ref "U6") (pin "3") (pinfunction "GND_3") (pintype "passive"))
      (node (ref "U6") (pin "6") (pinfunction "LV_6") (pintype "passive"))
      (node (ref "X-MAX") (pin "2") (pinfunction "2_2") (pintype "passive"))
      (node (ref "X-MIN") (pin "2") (pinfunction "2_2") (pintype "passive"))
      (node (ref "X1") (pin "2") (pinfunction "2_2") (pintype "passive"))
      (node (ref "X2") (pin "2") (pinfunction "2_2") (pintype "passive"))
      (node (ref "Y") (pin "2") (pinfunction "2_2") (pintype "passive"))
      (node (ref "Y-MAX") (pin "2") (pinfunction "2_2") (pintype "passive"))
      (node (ref "Y-MIN") (pin "2") (pinfunction "2_2") (pintype "passive"))
      (node (ref "Z") (pin "2") (pinfunction "2_2") (pintype "passive"))
      (node (ref "Z-MAX") (pin "2") (pinfunction "2_2") (pintype "passive"))
      (node (ref "Z-MIN") (pin "2") (pinfunction "2_2") (pintype "passive"))
    )
    (net (code "77") (name "Net-(AC110V-Pad1)") (class "Default")
      (node (ref "AC110V") (pin "1") (pinfunction "1_1") (pintype "passive"))
      (node (ref "F1") (pin "2") (pinfunction "2_2") (pintype "passive"))
      (node (ref "F2") (pin "2") (pinfunction "2_2") (pintype "passive"))
      (node (ref "F3") (pin "2") (pinfunction "2_2") (pintype "passive"))
    )
    (net (code "78") (name "Net-(AC110V-Pad2)") (class "Default")
      (node (ref "AC110V") (pin "2") (pinfunction "2_2") (pintype "passive"))
      (node (ref "BED") (pin "2") (pinfunction "2_2") (pintype "passive"))
      (node (ref "HEATER1") (pin "2") (pinfunction "2_2") (pintype "passive"))
      (node (ref "HEATER2") (pin "2") (pinfunction "2_2") (pintype "passive"))
      (node (ref "R13") (pin "2") (pinfunction "2_2") (pintype "passive"))
      (node (ref "R17") (pin "2") (pinfunction "2_2") (pintype "passive"))
      (node (ref "R21") (pin "2") (pinfunction "2_2") (pintype "passive"))
    )
    (net (code "79") (name "Net-(DS1-A)") (class "Default")
      (node (ref "DS1") (pin "1") (pinfunction "A_1") (pintype "passive"))
      (node (ref "R13") (pin "1") (pinfunction "1_1") (pintype "passive"))
    )
    (net (code "80") (name "Net-(DS1-K)") (class "Default")
      (node (ref "DS1") (pin "2") (pinfunction "K_2") (pintype "passive"))
      (node (ref "HEATER1") (pin "1") (pinfunction "1_1") (pintype "passive"))
      (node (ref "Q1") (pin "1") (pinfunction "M1_1") (pintype "passive"))
      (node (ref "R12") (pin "1") (pinfunction "1_1") (pintype "passive"))
    )
    (net (code "81") (name "Net-(DS2-A)") (class "Default")
      (node (ref "DS2") (pin "1") (pinfunction "A_1") (pintype "passive"))
      (node (ref "R17") (pin "1") (pinfunction "1_1") (pintype "passive"))
    )
    (net (code "82") (name "Net-(DS2-K)") (class "Default")
      (node (ref "DS2") (pin "2") (pinfunction "K_2") (pintype "passive"))
      (node (ref "HEATER2") (pin "1") (pinfunction "1_1") (pintype "passive"))
      (node (ref "Q2") (pin "1") (pinfunction "M1_1") (pintype "passive"))
      (node (ref "R16") (pin "1") (pinfunction "1_1") (pintype "passive"))
    )
    (net (code "83") (name "Net-(DS3-A)") (class "Default")
      (node (ref "DS3") (pin "1") (pinfunction "A_1") (pintype "passive"))
      (node (ref "R21") (pin "1") (pinfunction "1_1") (pintype "passive"))
    )
    (net (code "84") (name "Net-(DS3-K)") (class "Default")
      (node (ref "BED") (pin "1") (pinfunction "1_1") (pintype "passive"))
      (node (ref "DS3") (pin "2") (pinfunction "K_2") (pintype "passive"))
      (node (ref "Q3") (pin "1") (pinfunction "M1_1") (pintype "passive"))
      (node (ref "R20") (pin "1") (pinfunction "1_1") (pintype "passive"))
    )
    (net (code "85") (name "Net-(DS4-A)") (class "Default")
      (node (ref "DS4") (pin "1") (pinfunction "A_1") (pintype "passive"))
      (node (ref "R24") (pin "1") (pinfunction "1_1") (pintype "passive"))
    )
    (net (code "86") (name "Net-(P1-Pad3)") (class "Default")
      (node (ref "P1") (pin "3") (pinfunction "3_3") (pintype "passive"))
      (node (ref "R24") (pin "2") (pinfunction "2_2") (pintype "passive"))
    )
    (net (code "87") (name "Net-(P11-Pad1)") (class "Default")
      (node (ref "P11") (pin "1") (pinfunction "1_1") (pintype "passive"))
      (node (ref "R7") (pin "1") (pinfunction "1_1") (pintype "passive"))
    )
    (net (code "88") (name "Net-(P12-Pad14)") (class "Default")
      (node (ref "P12") (pin "14") (pinfunction "14_14") (pintype "passive"))
      (node (ref "P14") (pin "1") (pinfunction "1_1") (pintype "passive"))
      (node (ref "P14") (pin "2") (pinfunction "2_2") (pintype "passive"))
    )
    (net (code "89") (name "Net-(Q1-G)") (class "Default")
      (node (ref "Q1") (pin "3") (pinfunction "G_3") (pintype "passive"))
      (node (ref "R12") (pin "2") (pinfunction "2_2") (pintype "passive"))
      (node (ref "U1") (pin "4") (pinfunction "main_terminal_4") (pintype "passive"))
    )
    (net (code "90") (name "Net-(Q1-M2)") (class "Default")
      (node (ref "F1") (pin "1") (pinfunction "1_1") (pintype "passive"))
      (node (ref "Q1") (pin "2") (pinfunction "M2_2") (pintype "passive"))
      (node (ref "R11") (pin "2") (pinfunction "2_2") (pintype "passive"))
    )
    (net (code "91") (name "Net-(Q2-G)") (class "Default")
      (node (ref "Q2") (pin "3") (pinfunction "G_3") (pintype "passive"))
      (node (ref "R16") (pin "2") (pinfunction "2_2") (pintype "passive"))
      (node (ref "U2") (pin "4") (pinfunction "main_terminal_4") (pintype "passive"))
    )
    (net (code "92") (name "Net-(Q2-M2)") (class "Default")
      (node (ref "F2") (pin "1") (pinfunction "1_1") (pintype "passive"))
      (node (ref "Q2") (pin "2") (pinfunction "M2_2") (pintype "passive"))
      (node (ref "R15") (pin "2") (pinfunction "2_2") (pintype "passive"))
    )
    (net (code "93") (name "Net-(Q3-G)") (class "Default")
      (node (ref "Q3") (pin "3") (pinfunction "G_3") (pintype "passive"))
      (node (ref "R20") (pin "2") (pinfunction "2_2") (pintype "passive"))
      (node (ref "U3") (pin "4") (pinfunction "main_terminal_4") (pintype "passive"))
    )
    (net (code "94") (name "Net-(Q3-M2)") (class "Default")
      (node (ref "F3") (pin "1") (pinfunction "1_1") (pintype "passive"))
      (node (ref "Q3") (pin "2") (pinfunction "M2_2") (pintype "passive"))
      (node (ref "R19") (pin "2") (pinfunction "2_2") (pintype "passive"))
    )
    (net (code "95") (name "Net-(R5-Pad2)") (class "Default")
      (node (ref "R5") (pin "2") (pinfunction "2_2") (pintype "passive"))
      (node (ref "R6") (pin "1") (pinfunction "1_1") (pintype "passive"))
    )
    (net (code "96") (name "Net-(R8-Pad1)") (class "Default")
      (node (ref "R8") (pin "1") (pinfunction "1_1") (pintype "passive"))
      (node (ref "U5") (pin "1") (pinfunction "VOSTRIM_1") (pintype "passive"))
    )
    (net (code "97") (name "Net-(R9-Pad2)") (class "Default")
      (node (ref "R9") (pin "2") (pinfunction "2_2") (pintype "passive"))
      (node (ref "U5") (pin "8") (pinfunction "VOSTRIM_8") (pintype "passive"))
    )
    (net (code "98") (name "Net-(R11-Pad1)") (class "Default")
      (node (ref "R11") (pin "1") (pinfunction "1_1") (pintype "passive"))
      (node (ref "U1") (pin "6") (pinfunction "main_terminal_6") (pintype "passive"))
    )
    (net (code "99") (name "Net-(R15-Pad1)") (class "Default")
      (node (ref "R15") (pin "1") (pinfunction "1_1") (pintype "passive"))
      (node (ref "U2") (pin "6") (pinfunction "main_terminal_6") (pintype "passive"))
    )
    (net (code "100") (name "Net-(R19-Pad1)") (class "Default")
      (node (ref "R19") (pin "1") (pinfunction "1_1") (pintype "passive"))
      (node (ref "U3") (pin "6") (pinfunction "main_terminal_6") (pintype "passive"))
    )
    (net (code "101") (name "Net-(U1-A)") (class "Default")
      (node (ref "R10") (pin "2") (pinfunction "2_2") (pintype "passive"))
      (node (ref "U1") (pin "1") (pinfunction "A_1") (pintype "passive"))
    )
    (net (code "102") (name "Net-(U2-A)") (class "Default")
      (node (ref "R14") (pin "2") (pinfunction "2_2") (pintype "passive"))
      (node (ref "U2") (pin "1") (pinfunction "A_1") (pintype "passive"))
    )
    (net (code "103") (name "Net-(U3-A)") (class "Default")
      (node (ref "R18") (pin "2") (pinfunction "2_2") (pintype "passive"))
      (node (ref "U3") (pin "1") (pinfunction "A_1") (pintype "passive"))
    )
    (net (code "104") (name "Net-(U5-IN+)") (class "Default")
      (node (ref "C3") (pin "1") (pinfunction "1_1") (pintype "passive"))
      (node (ref "R7") (pin "2") (pinfunction "2_2") (pintype "passive"))
      (node (ref "U5") (pin "3") (pinfunction "IN+_3") (pintype "input"))
    )
    (net (code "105") (name "Net-(U5-IN-)") (class "Default")
      (node (ref "R4") (pin "2") (pinfunction "2_2") (pintype "passive"))
      (node (ref "R5") (pin "1") (pinfunction "1_1") (pintype "passive"))
      (node (ref "U5") (pin "2") (pinfunction "IN-_2") (pintype "input"))
    )
    (net (code "106") (name "Net-(U6-cap+)") (class "Default")
      (node (ref "C1") (pin "1") (pinfunction "1_1") (pintype "passive"))
      (node (ref "U6") (pin "2") (pinfunction "cap+_2") (pintype "passive"))
    )
    (net (code "107") (name "Net-(U6-cap-)") (class "Default")
      (node (ref "C1") (pin "2") (pinfunction "2_2") (pintype "passive"))
      (node (ref "U6") (pin "4") (pinfunction "cap-_4") (pintype "passive"))
    )
    (net (code "108") (name "VCC") (class "Default")
      (node (ref "P13") (pin "3") (pinfunction "3_3") (pintype "passive"))
    )
    (net (code "109") (name "unconnected-(AUX-3-Pad8)") (class "Default")
      (node (ref "AUX-3") (pin "8") (pinfunction "8_8") (pintype "passive"))
    )
    (net (code "110") (name "unconnected-(E0-Pad4)") (class "Default")
      (node (ref "E0") (pin "4") (pinfunction "4_4") (pintype "passive+no_connect"))
    )
    (net (code "111") (name "unconnected-(E1-Pad4)") (class "Default")
      (node (ref "E1") (pin "4") (pinfunction "4_4") (pintype "passive+no_connect"))
    )
    (net (code "112") (name "unconnected-(EXP2-Pad10)") (class "Default")
      (node (ref "EXP2") (pin "10") (pinfunction "10_10") (pintype "passive+no_connect"))
    )
    (net (code "113") (name "unconnected-(P1-Pad1)") (class "Default")
      (node (ref "P1") (pin "1") (pinfunction "1_1") (pintype "passive"))
    )
    (net (code "114") (name "unconnected-(P1-Pad2)") (class "Default")
      (node (ref "P1") (pin "2") (pinfunction "2_2") (pintype "passive"))
    )
    (net (code "115") (name "unconnected-(P2-Pad1)") (class "Default")
      (node (ref "P2") (pin "1") (pinfunction "1_1") (pintype "passive"))
    )
    (net (code "116") (name "unconnected-(P5-Pad9)") (class "Default")
      (node (ref "P5") (pin "9") (pinfunction "9_9") (pintype "passive"))
    )
    (net (code "117") (name "unconnected-(P6-Pad3)") (class "Default")
      (node (ref "P6") (pin "3") (pinfunction "3_3") (pintype "passive"))
    )
    (net (code "118") (name "unconnected-(P12-Pad8)") (class "Default")
      (node (ref "P12") (pin "8") (pinfunction "8_8") (pintype "passive"))
    )
    (net (code "119") (name "unconnected-(P12-Pad9)") (class "Default")
      (node (ref "P12") (pin "9") (pinfunction "9_9") (pintype "passive"))
    )
    (net (code "120") (name "unconnected-(U1-NC-Pad3)") (class "Default")
      (node (ref "U1") (pin "3") (pinfunction "NC_3") (pintype "passive+no_connect"))
    )
    (net (code "121") (name "unconnected-(U1-NC-Pad5)") (class "Default")
      (node (ref "U1") (pin "5") (pinfunction "NC_5") (pintype "passive+no_connect"))
    )
    (net (code "122") (name "unconnected-(U2-NC-Pad3)") (class "Default")
      (node (ref "U2") (pin "3") (pinfunction "NC_3") (pintype "passive+no_connect"))
    )
    (net (code "123") (name "unconnected-(U2-NC-Pad5)") (class "Default")
      (node (ref "U2") (pin "5") (pinfunction "NC_5") (pintype "passive+no_connect"))
    )
    (net (code "124") (name "unconnected-(U3-NC-Pad3)") (class "Default")
      (node (ref "U3") (pin "3") (pinfunction "NC_3") (pintype "passive+no_connect"))
    )
    (net (code "125") (name "unconnected-(U3-NC-Pad5)") (class "Default")
      (node (ref "U3") (pin "5") (pinfunction "NC_5") (pintype "passive+no_connect"))
    )
    (net (code "126") (name "unconnected-(U5-NC-Pad5)") (class "Default")
      (node (ref "U5") (pin "5") (pinfunction "NC_5") (pintype "passive+no_connect"))
    )
    (net (code "127") (name "unconnected-(U6-NC-Pad1)") (class "Default")
      (node (ref "U6") (pin "1") (pinfunction "NC_1") (pintype "passive"))
    )
    (net (code "128") (name "unconnected-(U6-OSC-Pad7)") (class "Default")
      (node (ref "U6") (pin "7") (pinfunction "OSC_7") (pintype "passive"))
    )
    (net (code "129") (name "unconnected-(X1-Pad4)") (class "Default")
      (node (ref "X1") (pin "4") (pinfunction "4_4") (pintype "passive+no_connect"))
    )
    (net (code "130") (name "unconnected-(X2-Pad4)") (class "Default")
      (node (ref "X2") (pin "4") (pinfunction "4_4") (pintype "passive+no_connect"))
    )
    (net (code "131") (name "unconnected-(Y-Pad4)") (class "Default")
      (node (ref "Y") (pin "4") (pinfunction "4_4") (pintype "passive+no_connect"))
    )
    (net (code "132") (name "unconnected-(Z-Pad4)") (class "Default")
      (node (ref "Z") (pin "4") (pinfunction "4_4") (pintype "passive+no_connect"))
    )
  )
)
